# schematic.net
KiCad netlist of a schematic drawn in Altium Designer
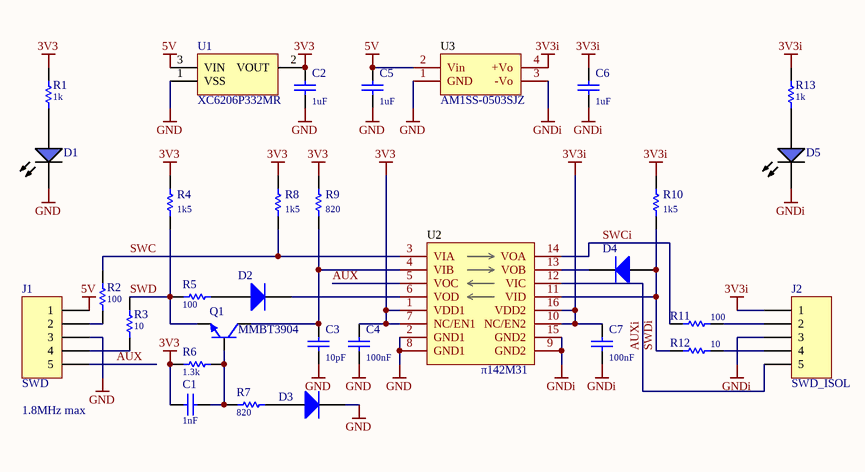
[diagram p0: schematic.SchDoc]

(export (version "E")
  (design (tool "Eeschema 10.0.6"))
  (components
    (comp (ref "C1")
      (value "1nF")
      (footprint "C0603")
      (description "100nF 50V 0603")
      (libsource (lib "Miscellaneous Devices") (part "CAP"))
    )
    (comp (ref "C2")
      (value "1uF")
      (footprint "C0603")
      (description "1uF 50V 0603")
      (libsource (lib "Miscellaneous Devices") (part "CAP"))
    )
    (comp (ref "C3")
      (value "10pF")
      (footprint "C0603")
      (description "100nF 50V 0603")
      (libsource (lib "Miscellaneous Devices") (part "CAP"))
    )
    (comp (ref "C4")
      (value "100nF")
      (footprint "C0603")
      (description "100nF 50V 0603")
      (libsource (lib "Miscellaneous Devices") (part "CAP"))
    )
    (comp (ref "C5")
      (value "1uF")
      (footprint "C0805")
      (description "1uF 50V 0805")
      (libsource (lib "Miscellaneous Devices") (part "CAP"))
    )
    (comp (ref "C6")
      (value "1uF")
      (footprint "C0603")
      (description "1uF 50V 0603")
      (libsource (lib "Miscellaneous Devices") (part "CAP"))
    )
    (comp (ref "C7")
      (value "100nF")
      (footprint "C0603")
      (description "100nF 50V 0603")
      (libsource (lib "Miscellaneous Devices") (part "CAP"))
    )
    (comp (ref "D1")
      (value "BLU")
      (footprint "LED-0603-BLU")
      (description "DIODE LED 0603 BLUE")
      (libsource (lib "Miscellaneous Devices") (part "LED-0603-BLUE"))
    )
    (comp (ref "D2")
      (value "DIODE")
      (footprint "SOD-123FL")
      (libsource (lib "Miscellaneous Devices") (part "US1M-13-F"))
    )
    (comp (ref "D3")
      (value "SCHOTTKY DIODE")
      (footprint "SOD-123FL")
      (libsource (lib "Miscellaneous Devices") (part "US1M-13-F"))
    )
    (comp (ref "D4")
      (value "SCHOTTKY DIODE")
      (footprint "SOD-123FL")
      (libsource (lib "Miscellaneous Devices") (part "US1M-13-F"))
    )
    (comp (ref "D5")
      (value "BLU")
      (footprint "LED-0603-BLU")
      (description "DIODE LED 0603 BLUE")
      (libsource (lib "Miscellaneous Devices") (part "LED-0603-BLUE"))
    )
    (comp (ref "J1")
      (value "SWD")
      (footprint "HDR-1X5_2.54")
      (libsource (lib "") (part "CONN MOLEX HDR-M 1x4_1"))
    )
    (comp (ref "J2")
      (value "SWD_ISOL")
      (footprint "HDR-1X5_2.54")
      (libsource (lib "Schlib1") (part "CONN MOLEX HDR-M 1x4"))
    )
    (comp (ref "Q1")
      (value "MMBT3904")
      (footprint "SOT-23")
      (description "MMBT3904 \"1AM\"")
      (libsource (lib "Miscellaneous Devices") (part "MMBT2222ALT1G"))
    )
    (comp (ref "R1")
      (value "1k")
      (footprint "R0603")
      (description "1k 0603")
      (libsource (lib "Miscellaneous Devices") (part "RES"))
    )
    (comp (ref "R2")
      (value "100")
      (footprint "R0603")
      (description "100 0603")
      (libsource (lib "Miscellaneous Devices") (part "RES"))
    )
    (comp (ref "R3")
      (value "10")
      (footprint "R0603")
      (description "10 0603")
      (libsource (lib "Miscellaneous Devices") (part "RES"))
    )
    (comp (ref "R4")
      (value "1k5")
      (footprint "R0603")
      (description "1.5k 0603")
      (libsource (lib "Miscellaneous Devices") (part "RES"))
    )
    (comp (ref "R5")
      (value "100")
      (footprint "R0603")
      (description "100R 0603")
      (libsource (lib "Miscellaneous Devices") (part "RES"))
    )
    (comp (ref "R6")
      (value "1.3k")
      (footprint "R0603")
      (description "1.3k 0603")
      (libsource (lib "Miscellaneous Devices") (part "RES"))
    )
    (comp (ref "R7")
      (value "820")
      (footprint "R0603")
      (description "820 0603")
      (libsource (lib "Miscellaneous Devices") (part "RES"))
    )
    (comp (ref "R8")
      (value "1k5")
      (footprint "R0603")
      (description "1.5k 0603")
      (libsource (lib "Miscellaneous Devices") (part "RES"))
    )
    (comp (ref "R9")
      (value "820")
      (footprint "R0603")
      (description "820 0603")
      (libsource (lib "Miscellaneous Devices") (part "RES"))
    )
    (comp (ref "R10")
      (value "1k5")
      (footprint "R0603")
      (description "1.5k 0603")
      (libsource (lib "Miscellaneous Devices") (part "RES"))
    )
    (comp (ref "R11")
      (value "100")
      (footprint "R0603")
      (description "100 0603")
      (libsource (lib "Miscellaneous Devices") (part "RES"))
    )
    (comp (ref "R12")
      (value "10")
      (footprint "R0603")
      (description "10 0603")
      (libsource (lib "Miscellaneous Devices") (part "RES"))
    )
    (comp (ref "R13")
      (value "1k")
      (footprint "R0603")
      (description "1k 0603")
      (libsource (lib "Miscellaneous Devices") (part "RES"))
    )
    (comp (ref "U1")
      (value "XC6206P332MR")
      (footprint "SOT-23")
      (libsource (lib "Schlib1") (part "Component_4_1"))
    )
    (comp (ref "U2") (value "π142M31") (footprint "SOIC-16") (libsource (lib "Schlib1") (part "π142M31")))
    (comp (ref "U3")
      (value "AM1SS-0503SJZ")
      (footprint "PWRM-TH_B2405S-1WR2")
      (libsource (lib "Schlib1") (part "B0503S-1WR2"))
    )
  )
  (nets
    (net (code "1") (name "/AUX") (class "Default")
      (node (ref "J1") (pin "5") (pinfunction "5_5") (pintype "passive"))
      (node (ref "U2") (pin "5") (pinfunction "VOC_5") (pintype "passive"))
    )
    (net (code "2") (name "/AUXi") (class "Default")
      (node (ref "J2") (pin "5") (pinfunction "5_5") (pintype "passive"))
      (node (ref "U2") (pin "12") (pinfunction "VIC_12") (pintype "passive"))
    )
    (net (code "3") (name "/SWC") (class "Default")
      (node (ref "R2") (pin "2") (pinfunction "2_2") (pintype "passive"))
      (node (ref "R8") (pin "1") (pinfunction "1_1") (pintype "passive"))
      (node (ref "U2") (pin "3") (pinfunction "VIA_3") (pintype "passive"))
    )
    (net (code "4") (name "/SWCi") (class "Default")
      (node (ref "R11") (pin "2") (pinfunction "2_2") (pintype "passive"))
      (node (ref "U2") (pin "14") (pinfunction "VOA_14") (pintype "passive"))
    )
    (net (code "5") (name "/SWD") (class "Default")
      (node (ref "Q1") (pin "2") (pinfunction "E_2") (pintype "passive"))
      (node (ref "R3") (pin "1") (pinfunction "1_1") (pintype "passive"))
      (node (ref "R4") (pin "1") (pinfunction "1_1") (pintype "passive"))
      (node (ref "R5") (pin "2") (pinfunction "2_2") (pintype "passive"))
    )
    (net (code "6") (name "/SWDi") (class "Default")
      (node (ref "D4") (pin "1") (pinfunction "A_1") (pintype "passive"))
      (node (ref "R10") (pin "1") (pinfunction "1_1") (pintype "passive"))
      (node (ref "R12") (pin "2") (pinfunction "2_2") (pintype "passive"))
      (node (ref "U2") (pin "11") (pinfunction "VID_11") (pintype "passive"))
    )
    (net (code "7") (name "3V3") (class "Default")
      (node (ref "C1") (pin "2") (pinfunction "2_2") (pintype "passive"))
      (node (ref "C2") (pin "2") (pinfunction "2_2") (pintype "passive"))
      (node (ref "C4") (pin "2") (pinfunction "2_2") (pintype "passive"))
      (node (ref "R1") (pin "2") (pinfunction "2_2") (pintype "passive"))
      (node (ref "R4") (pin "2") (pinfunction "2_2") (pintype "passive"))
      (node (ref "R6") (pin "2") (pinfunction "2_2") (pintype "passive"))
      (node (ref "R8") (pin "2") (pinfunction "2_2") (pintype "passive"))
      (node (ref "R9") (pin "2") (pinfunction "2_2") (pintype "passive"))
      (node (ref "U1") (pin "2") (pinfunction "VOUT_2") (pintype "passive"))
      (node (ref "U2") (pin "1") (pinfunction "VDD1_1") (pintype "passive"))
      (node (ref "U2") (pin "7") (pinfunction "NC/EN1_7") (pintype "passive"))
    )
    (net (code "8") (name "3V3i") (class "Default")
      (node (ref "C6") (pin "2") (pinfunction "2_2") (pintype "passive"))
      (node (ref "C7") (pin "2") (pinfunction "2_2") (pintype "passive"))
      (node (ref "J2") (pin "1") (pinfunction "1_1") (pintype "passive"))
      (node (ref "R10") (pin "2") (pinfunction "2_2") (pintype "passive"))
      (node (ref "R13") (pin "2") (pinfunction "2_2") (pintype "passive"))
      (node (ref "U2") (pin "10") (pinfunction "NC/EN2_10") (pintype "passive"))
      (node (ref "U2") (pin "16") (pinfunction "VDD2_16") (pintype "passive"))
      (node (ref "U3") (pin "4") (pinfunction "+Vo_4") (pintype "passive"))
    )
    (net (code "9") (name "5V") (class "Default")
      (node (ref "C5") (pin "2") (pinfunction "2_2") (pintype "passive"))
      (node (ref "J1") (pin "1") (pinfunction "1_1") (pintype "passive"))
      (node (ref "U1") (pin "3") (pinfunction "VIN_3") (pintype "passive"))
      (node (ref "U3") (pin "2") (pinfunction "Vin_2") (pintype "passive"))
    )
    (net (code "10") (name "GND") (class "Default")
      (node (ref "C2") (pin "1") (pinfunction "1_1") (pintype "passive"))
      (node (ref "C3") (pin "1") (pinfunction "1_1") (pintype "passive"))
      (node (ref "C4") (pin "1") (pinfunction "1_1") (pintype "passive"))
      (node (ref "C5") (pin "1") (pinfunction "1_1") (pintype "passive"))
      (node (ref "D1") (pin "2") (pinfunction "K_2") (pintype "passive"))
      (node (ref "D3") (pin "2") (pinfunction "K_2") (pintype "passive"))
      (node (ref "J1") (pin "3") (pinfunction "3_3") (pintype "passive"))
      (node (ref "U1") (pin "1") (pinfunction "VSS_1") (pintype "passive"))
      (node (ref "U2") (pin "2") (pinfunction "GND1_2") (pintype "passive"))
      (node (ref "U2") (pin "8") (pinfunction "GND1_8") (pintype "passive"))
      (node (ref "U3") (pin "1") (pinfunction "GND_1") (pintype "passive"))
    )
    (net (code "11") (name "GNDi") (class "Default")
      (node (ref "C6") (pin "1") (pinfunction "1_1") (pintype "passive"))
      (node (ref "C7") (pin "1") (pinfunction "1_1") (pintype "passive"))
      (node (ref "D5") (pin "2") (pinfunction "K_2") (pintype "passive"))
      (node (ref "J2") (pin "3") (pinfunction "3_3") (pintype "passive"))
      (node (ref "U2") (pin "15") (pinfunction "GND2_15") (pintype "passive"))
      (node (ref "U2") (pin "9") (pinfunction "GND2_9") (pintype "passive"))
      (node (ref "U3") (pin "3") (pinfunction "-Vo_3") (pintype "passive"))
    )
    (net (code "12") (name "Net-(D1-A)") (class "Default")
      (node (ref "D1") (pin "1") (pinfunction "A_1") (pintype "passive"))
      (node (ref "R1") (pin "1") (pinfunction "1_1") (pintype "passive"))
    )
    (net (code "13") (name "Net-(D2-A)") (class "Default")
      (node (ref "D2") (pin "1") (pinfunction "A_1") (pintype "passive"))
      (node (ref "R5") (pin "1") (pinfunction "1_1") (pintype "passive"))
    )
    (net (code "14") (name "Net-(D2-K)") (class "Default")
      (node (ref "D2") (pin "2") (pinfunction "K_2") (pintype "passive"))
      (node (ref "U2") (pin "6") (pinfunction "VOD_6") (pintype "passive"))
    )
    (net (code "15") (name "Net-(D3-A)") (class "Default")
      (node (ref "D3") (pin "1") (pinfunction "A_1") (pintype "passive"))
      (node (ref "R7") (pin "1") (pinfunction "1_1") (pintype "passive"))
    )
    (net (code "16") (name "Net-(D4-K)") (class "Default")
      (node (ref "D4") (pin "2") (pinfunction "K_2") (pintype "passive"))
      (node (ref "U2") (pin "13") (pinfunction "VOB_13") (pintype "passive"))
    )
    (net (code "17") (name "Net-(D5-A)") (class "Default")
      (node (ref "D5") (pin "1") (pinfunction "A_1") (pintype "passive"))
      (node (ref "R13") (pin "1") (pinfunction "1_1") (pintype "passive"))
    )
    (net (code "18") (name "Net-(J1-Pad2)") (class "Default")
      (node (ref "J1") (pin "2") (pinfunction "2_2") (pintype "passive"))
      (node (ref "R2") (pin "1") (pinfunction "1_1") (pintype "passive"))
    )
    (net (code "19") (name "Net-(J1-Pad4)") (class "Default")
      (node (ref "J1") (pin "4") (pinfunction "4_4") (pintype "passive"))
      (node (ref "R3") (pin "2") (pinfunction "2_2") (pintype "passive"))
    )
    (net (code "20") (name "Net-(J2-Pad2)") (class "Default")
      (node (ref "J2") (pin "2") (pinfunction "2_2") (pintype "passive"))
      (node (ref "R11") (pin "1") (pinfunction "1_1") (pintype "passive"))
    )
    (net (code "21") (name "Net-(J2-Pad4)") (class "Default")
      (node (ref "J2") (pin "4") (pinfunction "4_4") (pintype "passive"))
      (node (ref "R12") (pin "1") (pinfunction "1_1") (pintype "passive"))
    )
    (net (code "22") (name "Net-(Q1-B)") (class "Default")
      (node (ref "C1") (pin "1") (pinfunction "1_1") (pintype "passive"))
      (node (ref "Q1") (pin "1") (pinfunction "B_1") (pintype "passive"))
      (node (ref "R6") (pin "1") (pinfunction "1_1") (pintype "passive"))
      (node (ref "R7") (pin "2") (pinfunction "2_2") (pintype "passive"))
    )
    (net (code "23") (name "Net-(Q1-C)") (class "Default")
      (node (ref "C3") (pin "2") (pinfunction "2_2") (pintype "passive"))
      (node (ref "Q1") (pin "3") (pinfunction "C_3") (pintype "passive"))
      (node (ref "R9") (pin "1") (pinfunction "1_1") (pintype "passive"))
      (node (ref "U2") (pin "4") (pinfunction "VIB_4") (pintype "passive"))
    )
  )
)
